# ph.net
KiCad netlist of a schematic drawn in Altium Designer
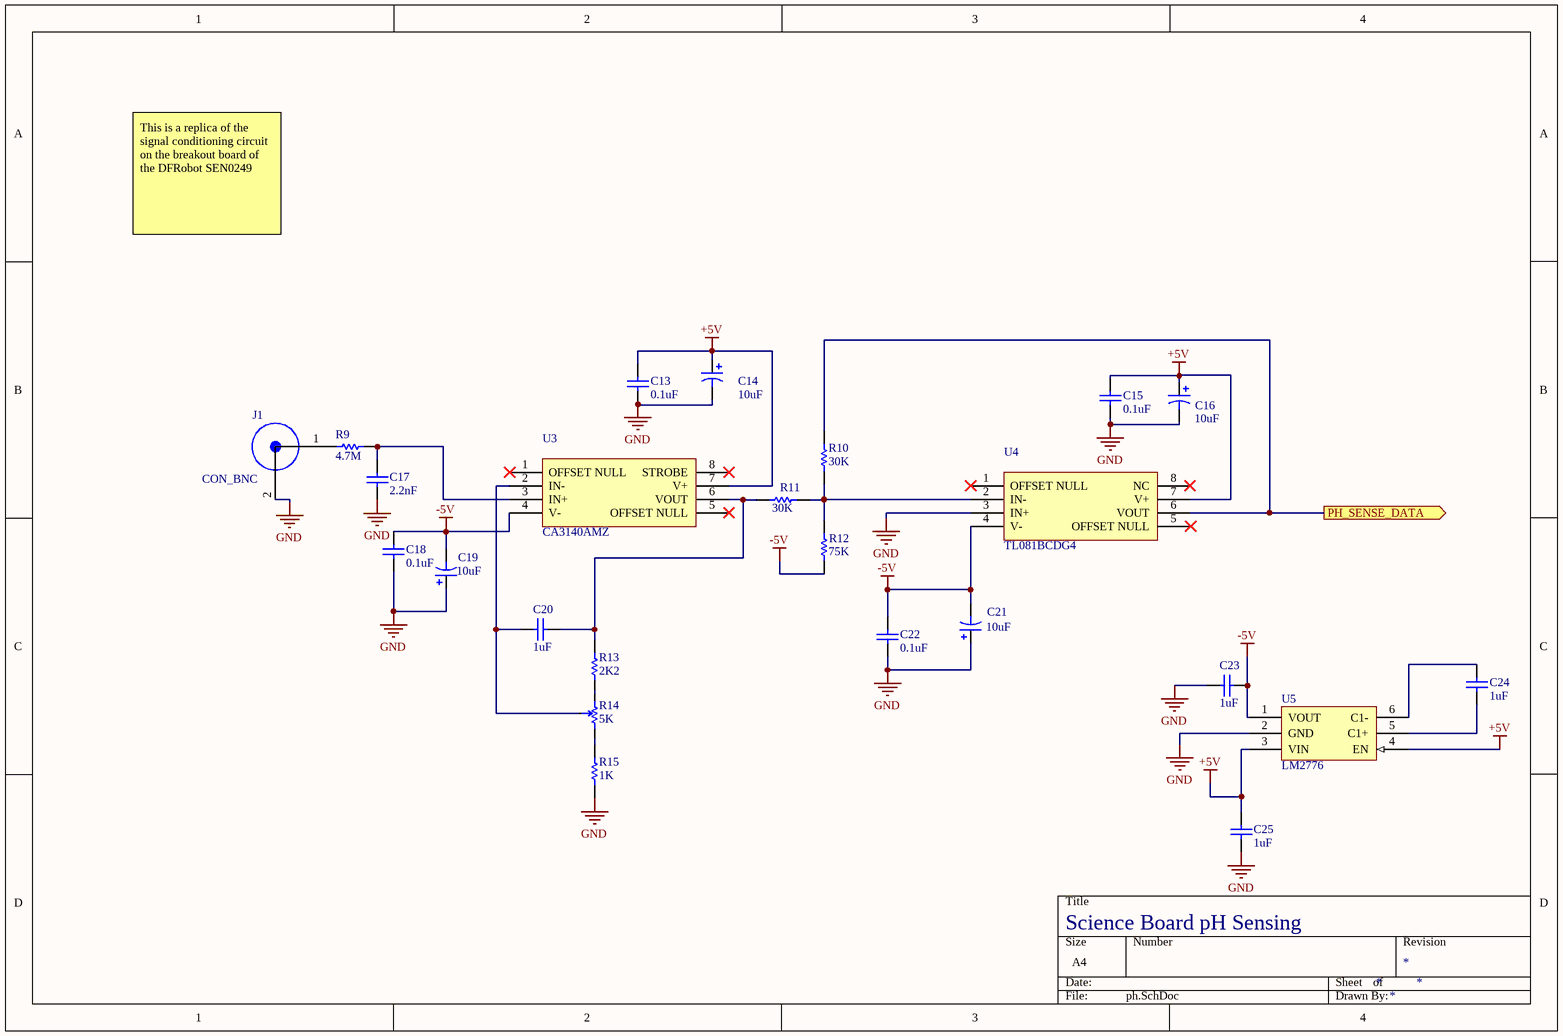
[diagram p0: ph.SchDoc]

(export (version "E")
  (design (tool "Eeschema 10.0.6"))
  (components
    (comp (ref "C13")
      (value "0.1uF")
      (footprint "CAPC0603(1608)55_N")
      (description "CAP CER 0.1UF 50V X7R 0603")
      (fields (field (name "PART NUMBER") "GCM188R71H104KA57D") (field (name "MANUFACTURER") "Yageo"))
      (libsource (lib "UWRT_Schematic_Library_2019") (part "CAP_0.1uF_50V_0603"))
    )
    (comp (ref "C14")
      (value "10uF")
      (footprint "AVX-CAPC3528_V")
      (description "Capacitor, Tantalum, 10uF 10% 20V MCCT-B (3528)")
      (fields (field (name "PART NUMBER") "CC0603MRX5R6BB106") (field (name "MANUFACTURER") "Yageo"))
      (libsource (lib "UWRT_Schematic_Library_2019") (part "CAP_10uF_0603_POL"))
    )
    (comp (ref "C15")
      (value "0.1uF")
      (footprint "CAPC0603(1608)55_N")
      (description "CAP CER 0.1UF 50V X7R 0603")
      (fields (field (name "PART NUMBER") "GCM188R71H104KA57D") (field (name "MANUFACTURER") "Yageo"))
      (libsource (lib "UWRT_Schematic_Library_2019") (part "CAP_0.1uF_50V_0603"))
    )
    (comp (ref "C16")
      (value "10uF")
      (footprint "AVX-CAPC3528_V")
      (description "Capacitor, Tantalum, 10uF 10% 20V MCCT-B (3528)")
      (fields (field (name "PART NUMBER") "CC0603MRX5R6BB106") (field (name "MANUFACTURER") "Yageo"))
      (libsource (lib "UWRT_Schematic_Library_2019") (part "CAP_10uF_0603_POL"))
    )
    (comp (ref "C17")
      (value "2.2nF")
      (footprint "CAPC0603(1608)55_N")
      (description "CAP CER 2.2NF 25V X7R 0603")
      (fields (field (name "PART NUMBER") "CC0603KRX7R8BB222") (field (name "MANUFACTURER") "Yageo"))
      (libsource (lib "UWRT_Schematic_Library_2019") (part "CAP_2.2nF_0603"))
    )
    (comp (ref "C18")
      (value "0.1uF")
      (footprint "CAPC0603(1608)55_N")
      (description "CAP CER 0.1UF 50V X7R 0603")
      (fields (field (name "PART NUMBER") "GCM188R71H104KA57D") (field (name "MANUFACTURER") "Yageo"))
      (libsource (lib "UWRT_Schematic_Library_2019") (part "CAP_0.1uF_50V_0603"))
    )
    (comp (ref "C19")
      (value "10uF")
      (footprint "AVX-CAPC3528_V")
      (description "Capacitor, Tantalum, 10uF 10% 20V MCCT-B (3528)")
      (fields (field (name "PART NUMBER") "CC0603MRX5R6BB106") (field (name "MANUFACTURER") "Yageo"))
      (libsource (lib "UWRT_Schematic_Library_2019") (part "CAP_10uF_0603_POL"))
    )
    (comp (ref "C20")
      (value "1uF")
      (footprint "CAPC0603(1608)55_N")
      (description "CAP CER 1UF 16V Y5V 0603")
      (fields (field (name "PART NUMBER") "CC0603ZRY5V7BB105") (field (name "MANUFACTURER") "Yageo"))
      (libsource (lib "UWRT_Schematic_Library_2019") (part "CAP_1uF_16V_0603"))
    )
    (comp (ref "C21")
      (value "10uF")
      (footprint "AVX-CAPC3528_V")
      (description "Capacitor, Tantalum, 10uF 10% 20V MCCT-B (3528)")
      (fields (field (name "PART NUMBER") "CC0603MRX5R6BB106") (field (name "MANUFACTURER") "Yageo"))
      (libsource (lib "UWRT_Schematic_Library_2019") (part "CAP_10uF_0603_POL"))
    )
    (comp (ref "C22")
      (value "0.1uF")
      (footprint "CAPC0603(1608)55_N")
      (description "CAP CER 0.1UF 50V X7R 0603")
      (fields (field (name "PART NUMBER") "GCM188R71H104KA57D") (field (name "MANUFACTURER") "Yageo"))
      (libsource (lib "UWRT_Schematic_Library_2019") (part "CAP_0.1uF_50V_0603"))
    )
    (comp (ref "C23")
      (value "1uF")
      (footprint "CAPC0603(1608)55_N")
      (description "CAP CER 1UF 16V Y5V 0603")
      (fields (field (name "PART NUMBER") "CC0603ZRY5V7BB105") (field (name "MANUFACTURER") "Yageo"))
      (libsource (lib "UWRT_Schematic_Library_2019") (part "CAP_1uF_16V_0603"))
    )
    (comp (ref "C24")
      (value "1uF")
      (footprint "CAPC0603(1608)55_N")
      (description "CAP CER 1UF 16V Y5V 0603")
      (fields (field (name "PART NUMBER") "CC0603ZRY5V7BB105") (field (name "MANUFACTURER") "Yageo"))
      (libsource (lib "UWRT_Schematic_Library_2019") (part "CAP_1uF_16V_0603"))
    )
    (comp (ref "C25")
      (value "1uF")
      (footprint "CAPC0603(1608)55_N")
      (description "CAP CER 1UF 16V Y5V 0603")
      (fields (field (name "PART NUMBER") "CC0603ZRY5V7BB105") (field (name "MANUFACTURER") "Yageo"))
      (libsource (lib "UWRT_Schematic_Library_2019") (part "CAP_1uF_16V_0603"))
    )
    (comp (ref "J1")
      (value "CON_BNC")
      (footprint "1-1337543-0")
      (fields (field (name "MANUFACTURER") "TE Connectivity"))
      (libsource (lib "UWRT_Schematic_Library_2019") (part "CON_BNC"))
    )
    (comp (ref "R9")
      (value "4.7M")
      (footprint "RESC0603(1608)_N")
      (description "RES SMD 4.7M OHM 1% 1/10W 0603")
      (fields (field (name "TOLERANCE") "1%") (field (name "MANUFACTURER") "Yageo"))
      (libsource (lib "UWRT_Schematic_Library_2019") (part "RES_4M7_0603"))
    )
    (comp (ref "R10")
      (value "30K")
      (footprint "RESC0603(1608)_N")
      (description "RES SMD 30K OHM 0.5% 1/10W 0603")
      (fields (field (name "MANUFACTURER") "Yageo") (field (name "TOLERANCE") "0.5%"))
      (libsource (lib "UWRT_Schematic_Library_2019") (part "RES_30K_0603"))
    )
    (comp (ref "R11")
      (value "30K")
      (footprint "RESC0603(1608)_N")
      (description "RES SMD 30K OHM 0.5% 1/10W 0603")
      (fields (field (name "MANUFACTURER") "Yageo") (field (name "TOLERANCE") "0.5%"))
      (libsource (lib "UWRT_Schematic_Library_2019") (part "RES_30K_0603"))
    )
    (comp (ref "R12")
      (value "75K")
      (footprint "RESC0603(1608)_N")
      (description "RES SMD 75K OHM 0.5% 1/10W 0603")
      (fields (field (name "MANUFACTURER") "Yageo") (field (name "TOLERANCE") "0.5%"))
      (libsource (lib "UWRT_Schematic_Library_2019") (part "RES_75K_0603"))
    )
    (comp (ref "R13")
      (value "2K2")
      (footprint "RESC0603(1608)_N")
      (description "RES SMD 2.2K OHM 1% 1/10W 0603")
      (fields (field (name "MANUFACTURER") "Yageo") (field (name "TOLERANCE") "1%"))
      (libsource (lib "UWRT_Schematic_Library_2019") (part "RES_2K2_0603"))
    )
    (comp (ref "R14")
      (value "5K")
      (footprint "3362P-1-502LF")
      (description "TRIMMER 5K OHM 0.5W PC PIN TOP")
      (fields (field (name "MANUFACTURER") "Bourns Inc.") (field (name "TOLERANCE") "10%"))
      (libsource (lib "UWRT_Schematic_Library_2019") (part "POT_5K"))
    )
    (comp (ref "R15")
      (value "1K")
      (footprint "RESC0603(1608)_N")
      (description "RES SMD 1K OHM 5% 1/10W 0603")
      (fields (field (name "TOLERANCE") "5%") (field (name "MANUFACTURER") "Yageo"))
      (libsource (lib "UWRT_Schematic_Library_2019") (part "RES_1K_0603"))
    )
    (comp (ref "U3")
      (value "CA3140AMZ")
      (footprint "CA3140AMZ")
      (description "4.5MHz, BiMOS Operational Amplifier with MOSFET Input/Bipolar Output")
      (libsource (lib "UWRT_Schematic_Library_2019") (part "CA3140AMZ"))
    )
    (comp (ref "U4")
      (value "TL081BCDG4")
      (footprint "TL081BCDG4")
      (description "IC OPAMP JFET 3MHZ 8SOIC")
      (libsource (lib "UWRT_Schematic_Library_2019") (part "TL081BCDG4"))
    )
    (comp (ref "U5")
      (value "LM2776")
      (footprint "SOT23-6")
      (description "LM2776 Switched Capacitor Inverter")
      (libsource (lib "UWRT_Schematic_Library_2019") (part "LM2776"))
    )
  )
  (nets
    (net (code "1") (name "+5V") (class "Default")
      (node (ref "C13") (pin "2") (pinfunction "2_2") (pintype "passive"))
      (node (ref "C14") (pin "1") (pinfunction "1_1") (pintype "passive"))
      (node (ref "C15") (pin "2") (pinfunction "2_2") (pintype "passive"))
      (node (ref "C16") (pin "1") (pinfunction "1_1") (pintype "passive"))
      (node (ref "C25") (pin "2") (pinfunction "2_2") (pintype "passive"))
      (node (ref "U3") (pin "7") (pinfunction "V+_7") (pintype "passive"))
      (node (ref "U4") (pin "7") (pinfunction "V+_7") (pintype "passive"))
      (node (ref "U5") (pin "3") (pinfunction "VIN_3") (pintype "power_in"))
      (node (ref "U5") (pin "4") (pinfunction "EN_4") (pintype "input"))
    )
    (net (code "2") (name "-5V") (class "Default")
      (node (ref "C18") (pin "2") (pinfunction "2_2") (pintype "passive"))
      (node (ref "C19") (pin "2") (pinfunction "2_2") (pintype "passive"))
      (node (ref "C21") (pin "2") (pinfunction "2_2") (pintype "passive"))
      (node (ref "C22") (pin "2") (pinfunction "2_2") (pintype "passive"))
      (node (ref "C23") (pin "1") (pinfunction "1_1") (pintype "passive"))
      (node (ref "R12") (pin "1") (pinfunction "1_1") (pintype "passive"))
      (node (ref "U3") (pin "4") (pinfunction "V-_4") (pintype "passive"))
      (node (ref "U4") (pin "4") (pinfunction "V-_4") (pintype "passive"))
      (node (ref "U5") (pin "1") (pinfunction "VOUT_1") (pintype "power_in"))
    )
    (net (code "3") (name "/PH_SENSE_DATA") (class "Default")
      (node (ref "R10") (pin "2") (pinfunction "2_2") (pintype "passive"))
      (node (ref "U4") (pin "6") (pinfunction "VOUT_6") (pintype "passive"))
    )
    (net (code "4") (name "GND") (class "Default")
      (node (ref "C13") (pin "1") (pinfunction "1_1") (pintype "passive"))
      (node (ref "C14") (pin "2") (pinfunction "2_2") (pintype "passive"))
      (node (ref "C15") (pin "1") (pinfunction "1_1") (pintype "passive"))
      (node (ref "C16") (pin "2") (pinfunction "2_2") (pintype "passive"))
      (node (ref "C17") (pin "1") (pinfunction "1_1") (pintype "passive"))
      (node (ref "C18") (pin "1") (pinfunction "1_1") (pintype "passive"))
      (node (ref "C19") (pin "1") (pinfunction "1_1") (pintype "passive"))
      (node (ref "C21") (pin "1") (pinfunction "1_1") (pintype "passive"))
      (node (ref "C22") (pin "1") (pinfunction "1_1") (pintype "passive"))
      (node (ref "C23") (pin "2") (pinfunction "2_2") (pintype "passive"))
      (node (ref "C25") (pin "1") (pinfunction "1_1") (pintype "passive"))
      (node (ref "J1") (pin "2") (pintype "passive"))
      (node (ref "R15") (pin "1") (pinfunction "1_1") (pintype "passive"))
      (node (ref "U4") (pin "3") (pinfunction "IN+_3") (pintype "passive"))
      (node (ref "U5") (pin "2") (pinfunction "GND_2") (pintype "passive"))
    )
    (net (code "5") (name "Net-(J1-Pad1)") (class "Default")
      (node (ref "J1") (pin "1") (pintype "passive"))
      (node (ref "R9") (pin "1") (pinfunction "1_1") (pintype "passive"))
    )
    (net (code "6") (name "Net-(R13-Pad1)") (class "Default")
      (node (ref "R13") (pin "1") (pinfunction "1_1") (pintype "passive"))
      (node (ref "R14") (pin "1") (pinfunction "1_1") (pintype "passive"))
    )
    (net (code "7") (name "Net-(R14-Pad2)") (class "Default")
      (node (ref "R14") (pin "2") (pinfunction "2_2") (pintype "passive"))
      (node (ref "R15") (pin "2") (pinfunction "2_2") (pintype "passive"))
    )
    (net (code "8") (name "Net-(U3-IN+)") (class "Default")
      (node (ref "C17") (pin "2") (pinfunction "2_2") (pintype "passive"))
      (node (ref "R9") (pin "2") (pinfunction "2_2") (pintype "passive"))
      (node (ref "U3") (pin "3") (pinfunction "IN+_3") (pintype "passive"))
    )
    (net (code "9") (name "Net-(U3-IN-)") (class "Default")
      (node (ref "C20") (pin "1") (pinfunction "1_1") (pintype "passive"))
      (node (ref "R14") (pin "3") (pinfunction "3_3") (pintype "passive"))
      (node (ref "U3") (pin "2") (pinfunction "IN-_2") (pintype "passive"))
    )
    (net (code "10") (name "Net-(U3-VOUT)") (class "Default")
      (node (ref "C20") (pin "2") (pinfunction "2_2") (pintype "passive"))
      (node (ref "R11") (pin "1") (pinfunction "1_1") (pintype "passive"))
      (node (ref "R13") (pin "2") (pinfunction "2_2") (pintype "passive"))
      (node (ref "U3") (pin "6") (pinfunction "VOUT_6") (pintype "passive"))
    )
    (net (code "11") (name "Net-(U4-IN-)") (class "Default")
      (node (ref "R10") (pin "1") (pinfunction "1_1") (pintype "passive"))
      (node (ref "R11") (pin "2") (pinfunction "2_2") (pintype "passive"))
      (node (ref "R12") (pin "2") (pinfunction "2_2") (pintype "passive"))
      (node (ref "U4") (pin "2") (pinfunction "IN-_2") (pintype "passive"))
    )
    (net (code "12") (name "Net-(U5-C1+)") (class "Default")
      (node (ref "C24") (pin "1") (pinfunction "1_1") (pintype "passive"))
      (node (ref "U5") (pin "5") (pinfunction "C1+_5") (pintype "power_in"))
    )
    (net (code "13") (name "Net-(U5-C1-)") (class "Default")
      (node (ref "C24") (pin "2") (pinfunction "2_2") (pintype "passive"))
      (node (ref "U5") (pin "6") (pinfunction "C1-_6") (pintype "power_in"))
    )
    (net (code "14") (name "unconnected-(U3-OFFSET_NULL-Pad1)") (class "Default")
      (node (ref "U3") (pin "1") (pinfunction "OFFSET_NULL_1") (pintype "passive"))
    )
    (net (code "15") (name "unconnected-(U3-OFFSET_NULL-Pad5)") (class "Default")
      (node (ref "U3") (pin "5") (pinfunction "OFFSET_NULL_5") (pintype "passive+no_connect"))
    )
    (net (code "16") (name "unconnected-(U3-STROBE-Pad8)") (class "Default")
      (node (ref "U3") (pin "8") (pinfunction "STROBE_8") (pintype "passive+no_connect"))
    )
    (net (code "17") (name "unconnected-(U4-NC-Pad8)") (class "Default")
      (node (ref "U4") (pin "8") (pinfunction "NC_8") (pintype "passive"))
    )
    (net (code "18") (name "unconnected-(U4-OFFSET_NULL-Pad1)") (class "Default")
      (node (ref "U4") (pin "1") (pinfunction "OFFSET_NULL_1") (pintype "passive+no_connect"))
    )
    (net (code "19") (name "unconnected-(U4-OFFSET_NULL-Pad5)") (class "Default")
      (node (ref "U4") (pin "5") (pinfunction "OFFSET_NULL_5") (pintype "passive"))
    )
  )
)
